# frc_operator_interface.net
KiCad netlist of a schematic drawn in EAGLE
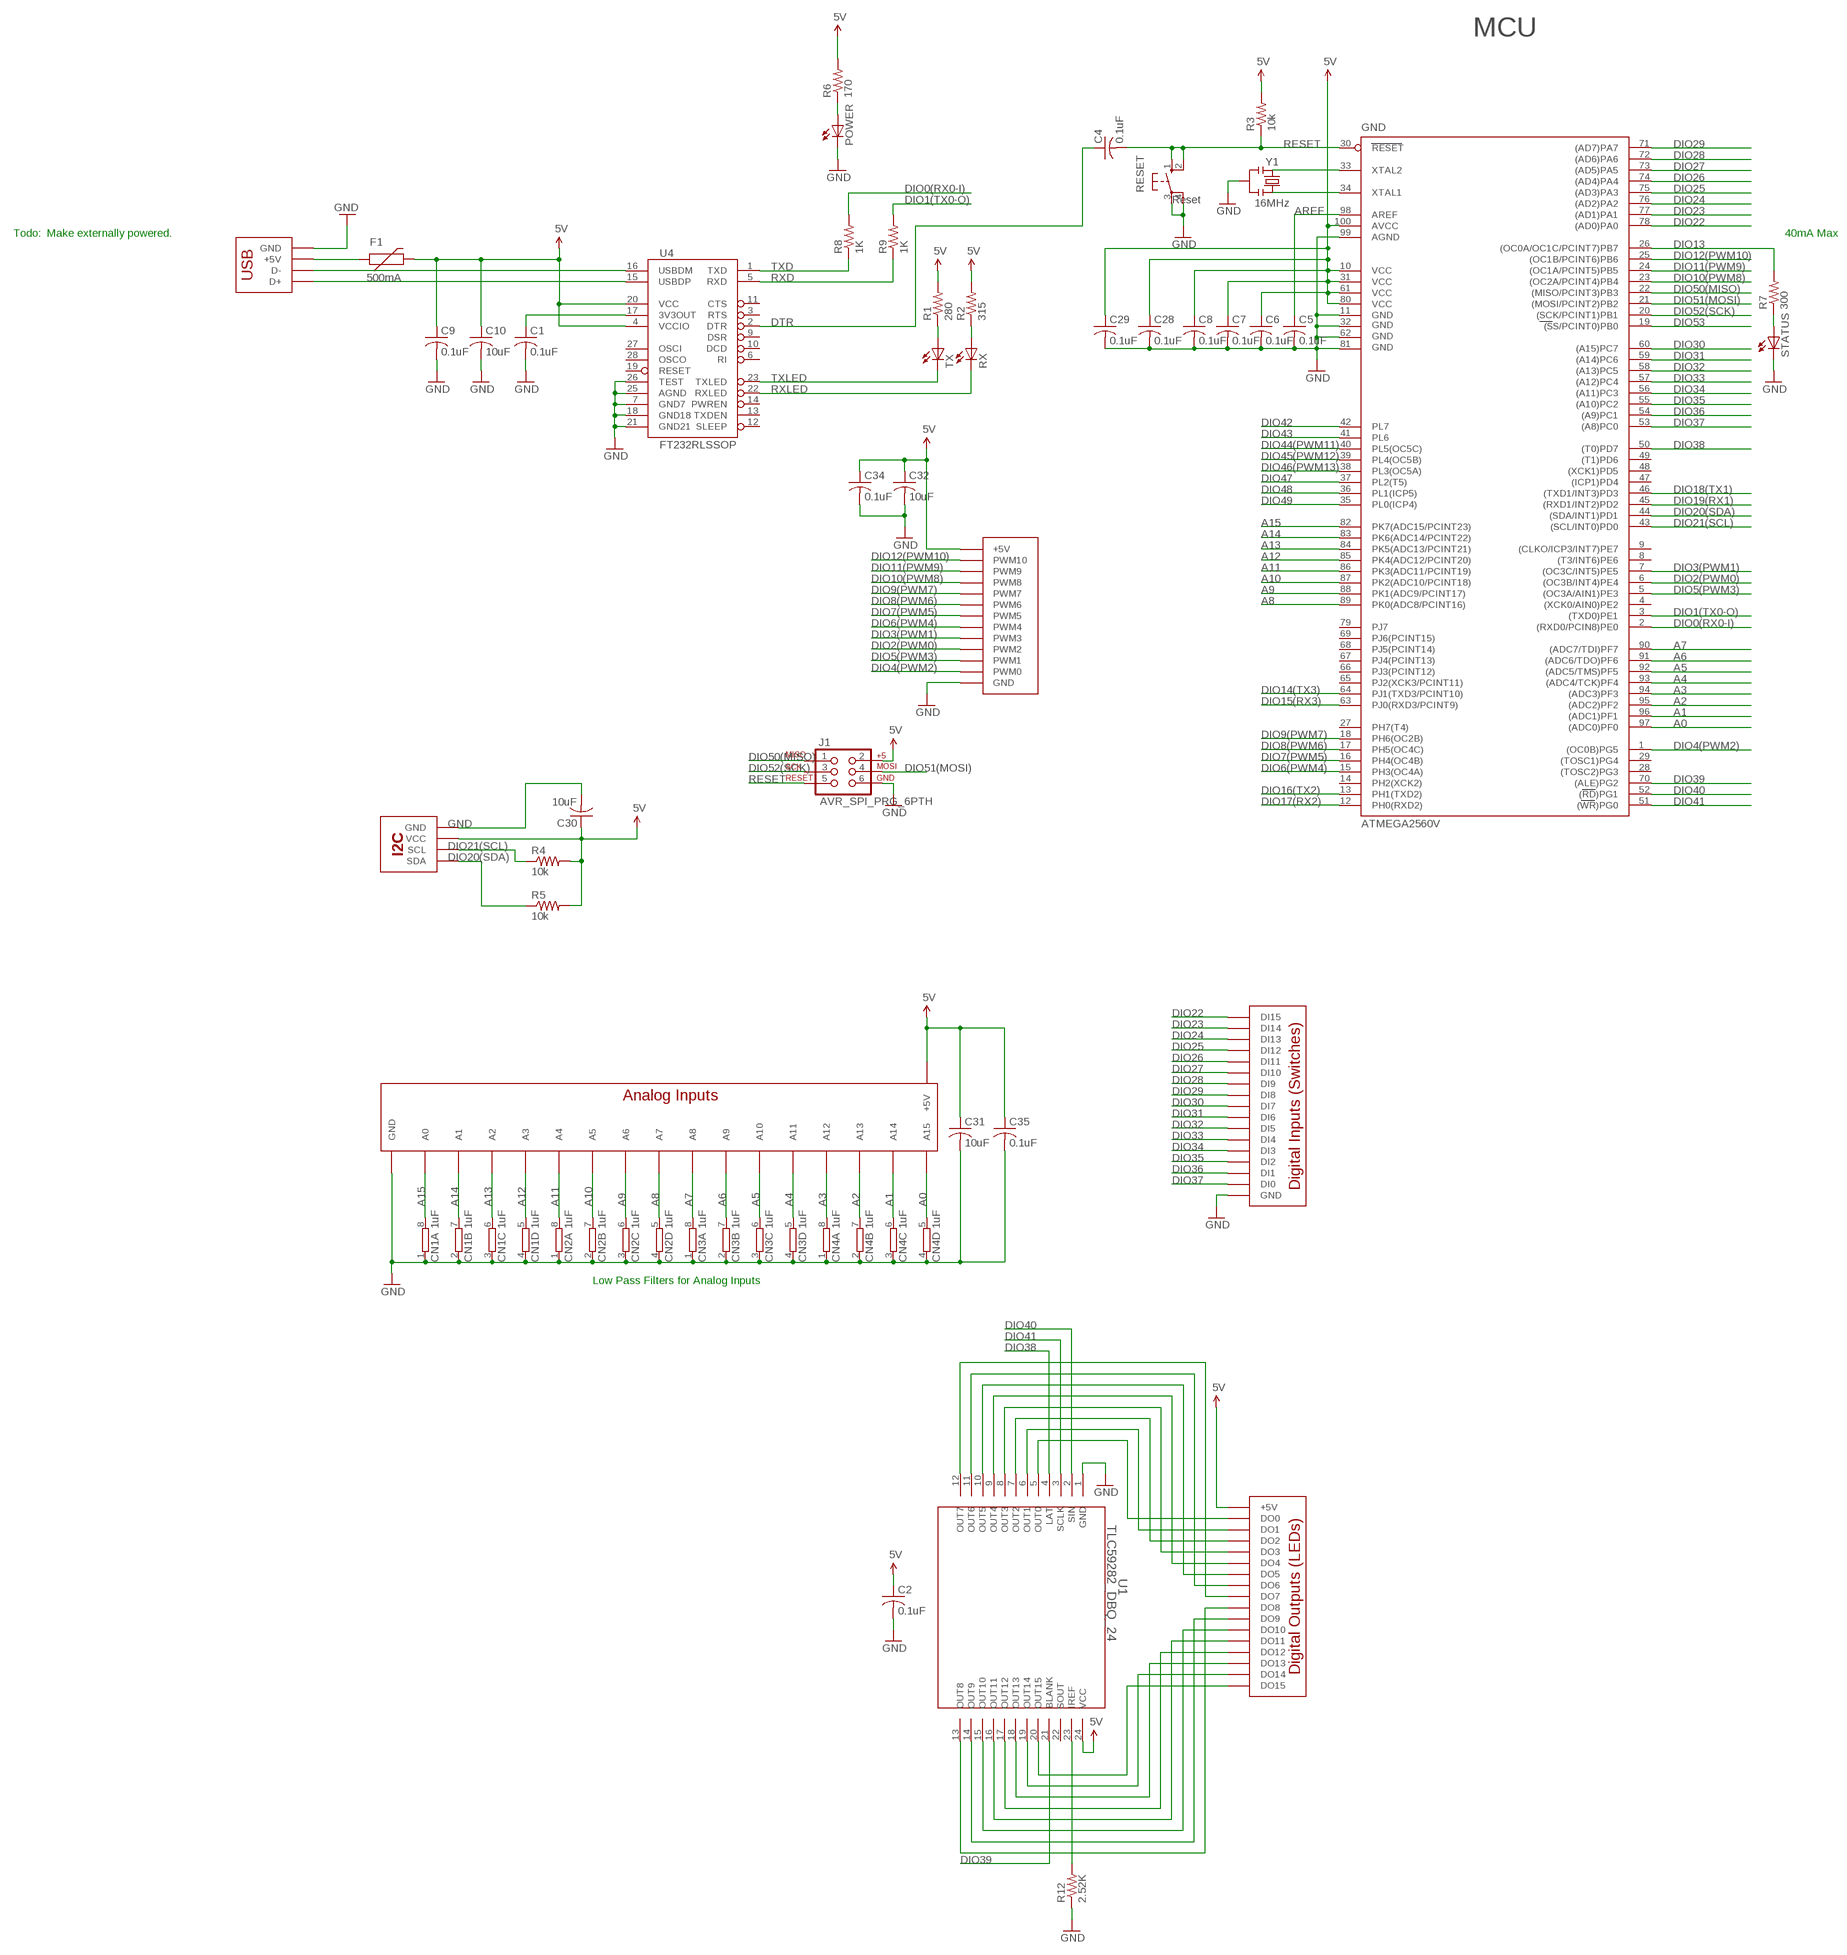
[diagram p0: schematic, sheet 1]

(export (version "E")
  (design (tool "Eeschema 10.0.6"))
  (components
    (comp (ref "C1")
      (value "0.1uF")
      (footprint "eagle-import:C1206")
      (libsource (lib "eagle-import") (part "C-USC1206"))
    )
    (comp (ref "C2")
      (value "0.1uF")
      (footprint "eagle-import:C1206")
      (libsource (lib "eagle-import") (part "C-USC1206"))
    )
    (comp (ref "C4")
      (value "0.1uF")
      (footprint "eagle-import:C1206")
      (libsource (lib "eagle-import") (part "C-USC1206"))
    )
    (comp (ref "C5")
      (value "0.1uF")
      (footprint "eagle-import:C1206")
      (libsource (lib "eagle-import") (part "C-USC1206"))
    )
    (comp (ref "C6")
      (value "0.1uF")
      (footprint "eagle-import:C1206")
      (libsource (lib "eagle-import") (part "C-USC1206"))
    )
    (comp (ref "C7")
      (value "0.1uF")
      (footprint "eagle-import:C1206")
      (libsource (lib "eagle-import") (part "C-USC1206"))
    )
    (comp (ref "C8")
      (value "0.1uF")
      (footprint "eagle-import:C1206")
      (libsource (lib "eagle-import") (part "C-USC1206"))
    )
    (comp (ref "C9")
      (value "0.1uF")
      (footprint "eagle-import:C1206")
      (libsource (lib "eagle-import") (part "C-USC1206"))
    )
    (comp (ref "C10")
      (value "10uF")
      (footprint "eagle-import:C1206")
      (libsource (lib "eagle-import") (part "C-USC1206"))
    )
    (comp (ref "C28")
      (value "0.1uF")
      (footprint "eagle-import:C1206")
      (libsource (lib "eagle-import") (part "C-USC1206"))
    )
    (comp (ref "C29")
      (value "0.1uF")
      (footprint "eagle-import:C1206")
      (libsource (lib "eagle-import") (part "C-USC1206"))
    )
    (comp (ref "C30")
      (value "10uF")
      (footprint "eagle-import:C1206")
      (libsource (lib "eagle-import") (part "C-USC1206"))
    )
    (comp (ref "C31")
      (value "10uF")
      (footprint "eagle-import:C1206")
      (libsource (lib "eagle-import") (part "C-USC1206"))
    )
    (comp (ref "C32")
      (value "10uF")
      (footprint "eagle-import:C1206")
      (libsource (lib "eagle-import") (part "C-USC1206"))
    )
    (comp (ref "C34")
      (value "0.1uF")
      (footprint "eagle-import:C1206")
      (libsource (lib "eagle-import") (part "C-USC1206"))
    )
    (comp (ref "C35")
      (value "0.1uF")
      (footprint "eagle-import:C1206")
      (libsource (lib "eagle-import") (part "C-USC1206"))
    )
    (comp (ref "CN1")
      (value "1uF")
      (footprint "eagle-import:EXB38V")
      (libsource (lib "eagle-import") (part "4R-NEXB38V"))
    )
    (comp (ref "CN2")
      (value "1uF")
      (footprint "eagle-import:EXB38V")
      (libsource (lib "eagle-import") (part "4R-NEXB38V"))
    )
    (comp (ref "CN3")
      (value "1uF")
      (footprint "eagle-import:EXB38V")
      (libsource (lib "eagle-import") (part "4R-NEXB38V"))
    )
    (comp (ref "CN4")
      (value "1uF")
      (footprint "eagle-import:EXB38V")
      (libsource (lib "eagle-import") (part "4R-NEXB38V"))
    )
    (comp (ref "F1")
      (value "500mA")
      (footprint "eagle-import:PTC-1206")
      (libsource (lib "eagle-import") (part "PTCSMD"))
    )
    (comp (ref "GND")
      (value "ATMEGA2560AU")
      (footprint "eagle-import:TQFP100")
      (libsource (lib "eagle-import") (part "ATMEGA2560AU"))
    )
    (comp (ref "J1")
      (value "AVR_SPI_PRG_6PTH")
      (footprint "eagle-import:2X3")
      (libsource (lib "eagle-import") (part "AVR_SPI_PRG_6PTH"))
    )
    (comp (ref "POWER")
      (value "LED3MM")
      (footprint "eagle-import:LED3MM")
      (libsource (lib "eagle-import") (part "LED3MM"))
    )
    (comp (ref "R1")
      (value "280")
      (footprint "eagle-import:M1206")
      (libsource (lib "eagle-import") (part "R-US_M1206"))
    )
    (comp (ref "R2")
      (value "315")
      (footprint "eagle-import:M1206")
      (libsource (lib "eagle-import") (part "R-US_M1206"))
    )
    (comp (ref "R3")
      (value "10k")
      (footprint "eagle-import:M1206")
      (libsource (lib "eagle-import") (part "R-US_M1206"))
    )
    (comp (ref "R4")
      (value "10k")
      (footprint "eagle-import:M1206")
      (libsource (lib "eagle-import") (part "R-US_M1206"))
    )
    (comp (ref "R5")
      (value "10k")
      (footprint "eagle-import:M1206")
      (libsource (lib "eagle-import") (part "R-US_M1206"))
    )
    (comp (ref "R6")
      (value "170")
      (footprint "eagle-import:M1206")
      (libsource (lib "eagle-import") (part "R-US_M1206"))
    )
    (comp (ref "R7")
      (value "300")
      (footprint "eagle-import:M1206")
      (libsource (lib "eagle-import") (part "R-US_M1206"))
    )
    (comp (ref "R8")
      (value "1K")
      (footprint "eagle-import:M1206")
      (libsource (lib "eagle-import") (part "R-US_M1206"))
    )
    (comp (ref "R9")
      (value "1K")
      (footprint "eagle-import:M1206")
      (libsource (lib "eagle-import") (part "R-US_M1206"))
    )
    (comp (ref "R12")
      (value "2.52K")
      (footprint "eagle-import:M1206")
      (libsource (lib "eagle-import") (part "R-US_M1206"))
    )
    (comp (ref "RESET")
      (value "10-XX")
      (footprint "eagle-import:B3F-10XX")
      (fields (field (name "MPN") "B3F-1000"))
      (libsource (lib "eagle-import") (part "10-XX"))
    )
    (comp (ref "RX")
      (value "LED3MM")
      (footprint "eagle-import:LED3MM")
      (libsource (lib "eagle-import") (part "LED3MM"))
    )
    (comp (ref "STATUS")
      (value "LED3MM")
      (footprint "eagle-import:LED3MM")
      (libsource (lib "eagle-import") (part "LED3MM"))
    )
    (comp (ref "TX")
      (value "LED3MM")
      (footprint "eagle-import:LED3MM")
      (libsource (lib "eagle-import") (part "LED3MM"))
    )
    (comp (ref "U$2")
      (value "DIGITALIN")
      (footprint "eagle-import:DIGITALIN")
      (libsource (lib "eagle-import") (part "DIGITALIN"))
    )
    (comp (ref "U$10")
      (value "PWMHEADER")
      (footprint "eagle-import:PWMHEADER")
      (libsource (lib "eagle-import") (part "PWMHEADER"))
    )
    (comp (ref "U$11")
      (value "DIGITALOUTPUTS")
      (footprint "eagle-import:DIGITALOUT")
      (libsource (lib "eagle-import") (part "DIGITALOUTPUTS"))
    )
    (comp (ref "U$12")
      (value "ANALOGHEADER")
      (footprint "eagle-import:ANALOGHEADER")
      (libsource (lib "eagle-import") (part "ANALOGHEADER"))
    )
    (comp (ref "U$14")
      (value "UE27BC54130-USB")
      (footprint "eagle-import:UE27BC54130-USB")
      (libsource (lib "eagle-import") (part "UE27BC54130-USB"))
    )
    (comp (ref "U$15")
      (value "I2CHEADER")
      (footprint "eagle-import:I2CHEADER")
      (libsource (lib "eagle-import") (part "I2CHEADER"))
    )
    (comp (ref "U1")
      (value "TLC59282_DBQ_24")
      (footprint "eagle-import:DBQ24")
      (fields
        (field (name "GENERIC_PART_NUMBER") "TLC59282")
        (field (name "MANUFACTURER") "Texas Instruments")
        (field (name "MANUFACTURER_PART_NUMBER") "tlc59282_dbq_24")
      )
      (libsource (lib "eagle-import") (part "TLC59282_DBQ_24"))
    )
    (comp (ref "U4")
      (value "FT232RLSSOP")
      (footprint "eagle-import:SSOP28DB")
      (libsource (lib "eagle-import") (part "FT232RLSSOP"))
    )
    (comp (ref "Y1")
      (value "RESONATORSMD")
      (footprint "eagle-import:RESONATOR-SMD")
      (libsource (lib "eagle-import") (part "RESONATORSMD"))
    )
  )
  (nets
    (net (code "1") (name "/A0") (class "Default")
      (node (ref "CN4") (pin "5") (pinfunction "2_5") (pintype "passive"))
      (node (ref "GND") (pin "97") (pinfunction "(ADC0)PF0_97") (pintype "bidirectional"))
      (node (ref "U$12") (pin "15") (pinfunction "A15_15") (pintype "bidirectional"))
    )
    (net (code "2") (name "/A1") (class "Default")
      (node (ref "CN4") (pin "6") (pinfunction "2_6") (pintype "passive"))
      (node (ref "GND") (pin "96") (pinfunction "(ADC1)PF1_96") (pintype "bidirectional"))
      (node (ref "U$12") (pin "14") (pinfunction "A14_14") (pintype "bidirectional"))
    )
    (net (code "3") (name "/A2") (class "Default")
      (node (ref "CN4") (pin "7") (pinfunction "2_7") (pintype "passive"))
      (node (ref "GND") (pin "95") (pinfunction "(ADC2)PF2_95") (pintype "bidirectional"))
      (node (ref "U$12") (pin "13") (pinfunction "A13_13") (pintype "bidirectional"))
    )
    (net (code "4") (name "/A3") (class "Default")
      (node (ref "CN4") (pin "8") (pinfunction "2_8") (pintype "passive"))
      (node (ref "GND") (pin "94") (pinfunction "(ADC3)PF3_94") (pintype "bidirectional"))
      (node (ref "U$12") (pin "12") (pinfunction "A12_12") (pintype "bidirectional"))
    )
    (net (code "5") (name "/A4") (class "Default")
      (node (ref "CN3") (pin "5") (pinfunction "2_5") (pintype "passive"))
      (node (ref "GND") (pin "93") (pinfunction "(ADC4/TCK)PF4_93") (pintype "bidirectional"))
      (node (ref "U$12") (pin "11") (pinfunction "A11_11") (pintype "bidirectional"))
    )
    (net (code "6") (name "/A5") (class "Default")
      (node (ref "CN3") (pin "6") (pinfunction "2_6") (pintype "passive"))
      (node (ref "GND") (pin "92") (pinfunction "(ADC5/TMS)PF5_92") (pintype "bidirectional"))
      (node (ref "U$12") (pin "10") (pinfunction "A10_10") (pintype "bidirectional"))
    )
    (net (code "7") (name "/A6") (class "Default")
      (node (ref "CN3") (pin "7") (pinfunction "2_7") (pintype "passive"))
      (node (ref "GND") (pin "91") (pinfunction "(ADC6/TDO)PF6_91") (pintype "bidirectional"))
      (node (ref "U$12") (pin "9") (pinfunction "A9_9") (pintype "bidirectional"))
    )
    (net (code "8") (name "/A7") (class "Default")
      (node (ref "CN3") (pin "8") (pinfunction "2_8") (pintype "passive"))
      (node (ref "GND") (pin "90") (pinfunction "(ADC7/TDI)PF7_90") (pintype "bidirectional"))
      (node (ref "U$12") (pin "8") (pinfunction "A8_8") (pintype "bidirectional"))
    )
    (net (code "9") (name "/A8") (class "Default")
      (node (ref "CN2") (pin "5") (pinfunction "2_5") (pintype "passive"))
      (node (ref "GND") (pin "89") (pinfunction "PK0(ADC8/PCINT16)_89") (pintype "bidirectional"))
      (node (ref "U$12") (pin "7") (pinfunction "A7_7") (pintype "bidirectional"))
    )
    (net (code "10") (name "/A9") (class "Default")
      (node (ref "CN2") (pin "6") (pinfunction "2_6") (pintype "passive"))
      (node (ref "GND") (pin "88") (pinfunction "PK1(ADC9/PCINT17)_88") (pintype "bidirectional"))
      (node (ref "U$12") (pin "6") (pinfunction "A6_6") (pintype "bidirectional"))
    )
    (net (code "11") (name "/A10") (class "Default")
      (node (ref "CN2") (pin "7") (pinfunction "2_7") (pintype "passive"))
      (node (ref "GND") (pin "87") (pinfunction "PK2(ADC10/PCINT18)_87") (pintype "bidirectional"))
      (node (ref "U$12") (pin "5") (pinfunction "A5_5") (pintype "bidirectional"))
    )
    (net (code "12") (name "/A11") (class "Default")
      (node (ref "CN2") (pin "8") (pinfunction "2_8") (pintype "passive"))
      (node (ref "GND") (pin "86") (pinfunction "PK3(ADC11/PCINT19)_86") (pintype "bidirectional"))
      (node (ref "U$12") (pin "4") (pinfunction "A4_4") (pintype "bidirectional"))
    )
    (net (code "13") (name "/A12") (class "Default")
      (node (ref "CN1") (pin "5") (pinfunction "2_5") (pintype "passive"))
      (node (ref "GND") (pin "85") (pinfunction "PK4(ADC12/PCINT20)_85") (pintype "bidirectional"))
      (node (ref "U$12") (pin "3") (pinfunction "A3_3") (pintype "bidirectional"))
    )
    (net (code "14") (name "/A13") (class "Default")
      (node (ref "CN1") (pin "6") (pinfunction "2_6") (pintype "passive"))
      (node (ref "GND") (pin "84") (pinfunction "PK5(ADC13/PCINT21)_84") (pintype "bidirectional"))
      (node (ref "U$12") (pin "2") (pinfunction "A2_2") (pintype "bidirectional"))
    )
    (net (code "15") (name "/A14") (class "Default")
      (node (ref "CN1") (pin "7") (pinfunction "2_7") (pintype "passive"))
      (node (ref "GND") (pin "83") (pinfunction "PK6(ADC14/PCINT22)_83") (pintype "bidirectional"))
      (node (ref "U$12") (pin "1") (pinfunction "A1_1") (pintype "bidirectional"))
    )
    (net (code "16") (name "/A15") (class "Default")
      (node (ref "CN1") (pin "8") (pinfunction "2_8") (pintype "passive"))
      (node (ref "GND") (pin "82") (pinfunction "PK7(ADC15/PCINT23)_82") (pintype "bidirectional"))
      (node (ref "U$12") (pin "0") (pinfunction "A0_0") (pintype "bidirectional"))
    )
    (net (code "17") (name "/AREF") (class "Default")
      (node (ref "C5") (pin "1") (pinfunction "1_1") (pintype "passive"))
      (node (ref "GND") (pin "98") (pinfunction "AREF_98") (pintype "bidirectional"))
    )
    (net (code "18") (name "/DIO0(RX0-I)") (class "Default")
      (node (ref "GND") (pin "2") (pinfunction "(RXD0/PCIN8)PE0_2") (pintype "bidirectional"))
      (node (ref "R8") (pin "2") (pinfunction "2_2") (pintype "passive"))
    )
    (net (code "19") (name "/DIO1(TX0-O)") (class "Default")
      (node (ref "GND") (pin "3") (pinfunction "(TXD0)PE1_3") (pintype "bidirectional"))
      (node (ref "R9") (pin "2") (pinfunction "2_2") (pintype "passive"))
    )
    (net (code "20") (name "/DIO2(PWM0)") (class "Default")
      (node (ref "GND") (pin "6") (pinfunction "(OC3B/INT4)PE4_6") (pintype "bidirectional"))
      (node (ref "U$10") (pin "2") (pinfunction "PWM2_2") (pintype "output"))
    )
    (net (code "21") (name "/DIO3(PWM1)") (class "Default")
      (node (ref "GND") (pin "7") (pinfunction "(OC3C/INT5)PE5_7") (pintype "bidirectional"))
      (node (ref "U$10") (pin "3") (pinfunction "PWM3_3") (pintype "output"))
    )
    (net (code "22") (name "/DIO4(PWM2)") (class "Default")
      (node (ref "GND") (pin "1") (pinfunction "(OC0B)PG5_1") (pintype "bidirectional"))
      (node (ref "U$10") (pin "0") (pinfunction "PWM0_0") (pintype "output"))
    )
    (net (code "23") (name "/DIO5(PWM3)") (class "Default")
      (node (ref "GND") (pin "5") (pinfunction "(OC3A/AIN1)PE3_5") (pintype "bidirectional"))
      (node (ref "U$10") (pin "1") (pinfunction "PWM1_1") (pintype "output"))
    )
    (net (code "24") (name "/DIO6(PWM4)") (class "Default")
      (node (ref "GND") (pin "15") (pinfunction "PH3(OC4A)_15") (pintype "bidirectional"))
      (node (ref "U$10") (pin "4") (pinfunction "PWM4_4") (pintype "output"))
    )
    (net (code "25") (name "/DIO7(PWM5)") (class "Default")
      (node (ref "GND") (pin "16") (pinfunction "PH4(OC4B)_16") (pintype "bidirectional"))
      (node (ref "U$10") (pin "5") (pinfunction "PWM5_5") (pintype "output"))
    )
    (net (code "26") (name "/DIO8(PWM6)") (class "Default")
      (node (ref "GND") (pin "17") (pinfunction "PH5(OC4C)_17") (pintype "bidirectional"))
      (node (ref "U$10") (pin "6") (pinfunction "PWM6_6") (pintype "output"))
    )
    (net (code "27") (name "/DIO9(PWM7)") (class "Default")
      (node (ref "GND") (pin "18") (pinfunction "PH6(OC2B)_18") (pintype "bidirectional"))
      (node (ref "U$10") (pin "7") (pinfunction "PWM7_7") (pintype "output"))
    )
    (net (code "28") (name "/DIO10(PWM8)") (class "Default")
      (node (ref "GND") (pin "23") (pinfunction "(OC2A/PCINT4)PB4_23") (pintype "bidirectional"))
      (node (ref "U$10") (pin "8") (pinfunction "PWM8_8") (pintype "output"))
    )
    (net (code "29") (name "/DIO11(PWM9)") (class "Default")
      (node (ref "GND") (pin "24") (pinfunction "(OC1A/PCINT5)PB5_24") (pintype "bidirectional"))
      (node (ref "U$10") (pin "9") (pinfunction "PWM9_9") (pintype "output"))
    )
    (net (code "30") (name "/DIO12(PWM10)") (class "Default")
      (node (ref "GND") (pin "25") (pinfunction "(OC1B/PCINT6)PB6_25") (pintype "bidirectional"))
      (node (ref "U$10") (pin "10") (pinfunction "PWM10_10") (pintype "output"))
    )
    (net (code "31") (name "/DIO13") (class "Default")
      (node (ref "GND") (pin "26") (pinfunction "(OC0A/OC1C/PCINT7)PB7_26") (pintype "bidirectional"))
      (node (ref "R7") (pin "2") (pinfunction "2_2") (pintype "passive"))
    )
    (net (code "32") (name "/DIO14(TX3)") (class "Default")
      (node (ref "GND") (pin "64") (pinfunction "PJ1(TXD3/PCINT10)_64") (pintype "bidirectional"))
    )
    (net (code "33") (name "/DIO15(RX3)") (class "Default")
      (node (ref "GND") (pin "63") (pinfunction "PJ0(RXD3/PCINT9)_63") (pintype "bidirectional"))
    )
    (net (code "34") (name "/DIO16(TX2)") (class "Default")
      (node (ref "GND") (pin "13") (pinfunction "PH1(TXD2)_13") (pintype "bidirectional"))
    )
    (net (code "35") (name "/DIO17(RX2)") (class "Default")
      (node (ref "GND") (pin "12") (pinfunction "PH0(RXD2)_12") (pintype "bidirectional"))
    )
    (net (code "36") (name "/DIO18(TX1)") (class "Default")
      (node (ref "GND") (pin "46") (pinfunction "(TXD1/INT3)PD3_46") (pintype "bidirectional"))
    )
    (net (code "37") (name "/DIO19(RX1)") (class "Default")
      (node (ref "GND") (pin "45") (pinfunction "(RXD1/INT2)PD2_45") (pintype "bidirectional"))
    )
    (net (code "38") (name "/DIO20(SDA)") (class "Default")
      (node (ref "GND") (pin "44") (pinfunction "(SDA/INT1)PD1_44") (pintype "bidirectional"))
      (node (ref "R5") (pin "1") (pinfunction "1_1") (pintype "passive"))
      (node (ref "U$15") (pin "SDA@0") (pinfunction "SDA_SDA@0") (pintype "bidirectional"))
      (node (ref "U$15") (pin "SDA@1") (pinfunction "SDA_SDA@1") (pintype "bidirectional"))
      (node (ref "U$15") (pin "SDA@2") (pinfunction "SDA_SDA@2") (pintype "bidirectional"))
      (node (ref "U$15") (pin "SDA@3") (pinfunction "SDA_SDA@3") (pintype "bidirectional"))
    )
    (net (code "39") (name "/DIO21(SCL)") (class "Default")
      (node (ref "GND") (pin "43") (pinfunction "(SCL/INT0)PD0_43") (pintype "bidirectional"))
      (node (ref "R4") (pin "1") (pinfunction "1_1") (pintype "passive"))
      (node (ref "U$15") (pin "SCL@0") (pinfunction "SCL_SCL@0") (pintype "bidirectional"))
      (node (ref "U$15") (pin "SCL@1") (pinfunction "SCL_SCL@1") (pintype "bidirectional"))
      (node (ref "U$15") (pin "SCL@2") (pinfunction "SCL_SCL@2") (pintype "bidirectional"))
      (node (ref "U$15") (pin "SCL@3") (pinfunction "SCL_SCL@3") (pintype "bidirectional"))
    )
    (net (code "40") (name "/DIO22") (class "Default")
      (node (ref "GND") (pin "78") (pinfunction "(AD0)PA0_78") (pintype "bidirectional"))
      (node (ref "U$2") (pin "DI15") (pinfunction "DI15_DI15") (pintype "bidirectional"))
    )
    (net (code "41") (name "/DIO23") (class "Default")
      (node (ref "GND") (pin "77") (pinfunction "(AD1)PA1_77") (pintype "bidirectional"))
      (node (ref "U$2") (pin "DI14") (pinfunction "DI14_DI14") (pintype "bidirectional"))
    )
    (net (code "42") (name "/DIO24") (class "Default")
      (node (ref "GND") (pin "76") (pinfunction "(AD2)PA2_76") (pintype "bidirectional"))
      (node (ref "U$2") (pin "DI13") (pinfunction "DI13_DI13") (pintype "bidirectional"))
    )
    (net (code "43") (name "/DIO25") (class "Default")
      (node (ref "GND") (pin "75") (pinfunction "(AD3)PA3_75") (pintype "bidirectional"))
      (node (ref "U$2") (pin "DI12") (pinfunction "DI12_DI12") (pintype "bidirectional"))
    )
    (net (code "44") (name "/DIO26") (class "Default")
      (node (ref "GND") (pin "74") (pinfunction "(AD4)PA4_74") (pintype "bidirectional"))
      (node (ref "U$2") (pin "DI11") (pinfunction "DI11_DI11") (pintype "bidirectional"))
    )
    (net (code "45") (name "/DIO27") (class "Default")
      (node (ref "GND") (pin "73") (pinfunction "(AD5)PA5_73") (pintype "bidirectional"))
      (node (ref "U$2") (pin "DI10") (pinfunction "DI10_DI10") (pintype "bidirectional"))
    )
    (net (code "46") (name "/DIO28") (class "Default")
      (node (ref "GND") (pin "72") (pinfunction "(AD6)PA6_72") (pintype "bidirectional"))
      (node (ref "U$2") (pin "DI9") (pinfunction "DI9_DI9") (pintype "bidirectional"))
    )
    (net (code "47") (name "/DIO29") (class "Default")
      (node (ref "GND") (pin "71") (pinfunction "(AD7)PA7_71") (pintype "bidirectional"))
      (node (ref "U$2") (pin "DI8") (pinfunction "DI8_DI8") (pintype "bidirectional"))
    )
    (net (code "48") (name "/DIO30") (class "Default")
      (node (ref "GND") (pin "60") (pinfunction "(A15)PC7_60") (pintype "bidirectional"))
      (node (ref "U$2") (pin "DI7") (pinfunction "DI7_DI7") (pintype "bidirectional"))
    )
    (net (code "49") (name "/DIO31") (class "Default")
      (node (ref "GND") (pin "59") (pinfunction "(A14)PC6_59") (pintype "bidirectional"))
      (node (ref "U$2") (pin "DI6") (pinfunction "DI6_DI6") (pintype "bidirectional"))
    )
    (net (code "50") (name "/DIO32") (class "Default")
      (node (ref "GND") (pin "58") (pinfunction "(A13)PC5_58") (pintype "bidirectional"))
      (node (ref "U$2") (pin "DI5") (pinfunction "DI5_DI5") (pintype "bidirectional"))
    )
    (net (code "51") (name "/DIO33") (class "Default")
      (node (ref "GND") (pin "57") (pinfunction "(A12)PC4_57") (pintype "bidirectional"))
      (node (ref "U$2") (pin "DI4") (pinfunction "DI4_DI4") (pintype "bidirectional"))
    )
    (net (code "52") (name "/DIO34") (class "Default")
      (node (ref "GND") (pin "56") (pinfunction "(A11)PC3_56") (pintype "bidirectional"))
      (node (ref "U$2") (pin "DI3") (pinfunction "DI3_DI3") (pintype "bidirectional"))
    )
    (net (code "53") (name "/DIO35") (class "Default")
      (node (ref "GND") (pin "55") (pinfunction "(A10)PC2_55") (pintype "bidirectional"))
      (node (ref "U$2") (pin "DI2") (pinfunction "DI2_DI2") (pintype "bidirectional"))
    )
    (net (code "54") (name "/DIO36") (class "Default")
      (node (ref "GND") (pin "54") (pinfunction "(A9)PC1_54") (pintype "bidirectional"))
      (node (ref "U$2") (pin "DI1") (pinfunction "DI1_DI1") (pintype "bidirectional"))
    )
    (net (code "55") (name "/DIO37") (class "Default")
      (node (ref "GND") (pin "53") (pinfunction "(A8)PC0_53") (pintype "bidirectional"))
      (node (ref "U$2") (pin "DI0") (pinfunction "DI0_DI0") (pintype "bidirectional"))
    )
    (net (code "56") (name "/DIO38") (class "Default")
      (node (ref "GND") (pin "50") (pinfunction "(T0)PD7_50") (pintype "bidirectional"))
      (node (ref "U1") (pin "4") (pinfunction "LAT_4") (pintype "input"))
    )
    (net (code "57") (name "/DIO39") (class "Default")
      (node (ref "GND") (pin "70") (pinfunction "(ALE)PG2_70") (pintype "bidirectional"))
      (node (ref "U1") (pin "21") (pinfunction "BLANK_21") (pintype "input"))
    )
    (net (code "58") (name "/DIO40") (class "Default")
      (node (ref "GND") (pin "52") (pinfunction "(RD)PG1_52") (pintype "bidirectional"))
      (node (ref "U1") (pin "2") (pinfunction "SIN_2") (pintype "input"))
    )
    (net (code "59") (name "/DIO41") (class "Default")
      (node (ref "GND") (pin "51") (pinfunction "(WR)PG0_51") (pintype "bidirectional"))
      (node (ref "U1") (pin "3") (pinfunction "SCLK_3") (pintype "input"))
    )
    (net (code "60") (name "/DIO42") (class "Default")
      (node (ref "GND") (pin "42") (pinfunction "PL7_42") (pintype "bidirectional"))
    )
    (net (code "61") (name "/DIO43") (class "Default")
      (node (ref "GND") (pin "41") (pinfunction "PL6_41") (pintype "bidirectional"))
    )
    (net (code "62") (name "/DIO44(PWM11)") (class "Default")
      (node (ref "GND") (pin "40") (pinfunction "PL5(OC5C)_40") (pintype "bidirectional"))
    )
    (net (code "63") (name "/DIO45(PWM12)") (class "Default")
      (node (ref "GND") (pin "39") (pinfunction "PL4(OC5B)_39") (pintype "bidirectional"))
    )
    (net (code "64") (name "/DIO46(PWM13)") (class "Default")
      (node (ref "GND") (pin "38") (pinfunction "PL3(OC5A)_38") (pintype "bidirectional"))
    )
    (net (code "65") (name "/DIO47") (class "Default")
      (node (ref "GND") (pin "37") (pinfunction "PL2(T5)_37") (pintype "bidirectional"))
    )
    (net (code "66") (name "/DIO48") (class "Default")
      (node (ref "GND") (pin "36") (pinfunction "PL1(ICP5)_36") (pintype "bidirectional"))
    )
    (net (code "67") (name "/DIO49") (class "Default")
      (node (ref "GND") (pin "35") (pinfunction "PL0(ICP4)_35") (pintype "bidirectional"))
    )
    (net (code "68") (name "/DIO50(MISO)") (class "Default")
      (node (ref "GND") (pin "22") (pinfunction "(MISO/PCINT3)PB3_22") (pintype "bidirectional"))
      (node (ref "J1") (pin "1") (pinfunction "1_1") (pintype "passive"))
    )
    (net (code "69") (name "/DIO51(MOSI)") (class "Default")
      (node (ref "GND") (pin "21") (pinfunction "(MOSI/PCINT2)PB2_21") (pintype "bidirectional"))
      (node (ref "J1") (pin "4") (pinfunction "4_4") (pintype "passive"))
    )
    (net (code "70") (name "/DIO52(SCK)") (class "Default")
      (node (ref "GND") (pin "20") (pinfunction "(SCK/PCINT1)PB1_20") (pintype "bidirectional"))
      (node (ref "J1") (pin "3") (pinfunction "3_3") (pintype "passive"))
    )
    (net (code "71") (name "/DIO53") (class "Default")
      (node (ref "GND") (pin "19") (pinfunction "(SS/PCINT0)PB0_19") (pintype "bidirectional"))
    )
    (net (code "72") (name "/DTR") (class "Default")
      (node (ref "C4") (pin "1") (pinfunction "1_1") (pintype "passive"))
      (node (ref "U4") (pin "2") (pinfunction "DTR_2") (pintype "output"))
    )
    (net (code "73") (name "/RESET") (class "Default")
      (node (ref "C4") (pin "2") (pinfunction "2_2") (pintype "passive"))
      (node (ref "GND") (pin "30") (pinfunction "RESET_30") (pintype "input"))
      (node (ref "J1") (pin "5") (pinfunction "5_5") (pintype "passive"))
      (node (ref "R3") (pin "1") (pinfunction "1_1") (pintype "passive"))
      (node (ref "RESET") (pin "1") (pinfunction "S_1") (pintype "passive"))
      (node (ref "RESET") (pin "2") (pinfunction "S1_2") (pintype "passive"))
    )
    (net (code "74") (name "/RXD") (class "Default")
      (node (ref "R9") (pin "1") (pinfunction "1_1") (pintype "passive"))
      (node (ref "U4") (pin "5") (pinfunction "RXD_5") (pintype "input"))
    )
    (net (code "75") (name "/RXLED") (class "Default")
      (node (ref "RX") (pin "K") (pinfunction "C_K") (pintype "passive"))
      (node (ref "U4") (pin "22") (pinfunction "RXLED_22") (pintype "input"))
    )
    (net (code "76") (name "/TXD") (class "Default")
      (node (ref "R8") (pin "1") (pinfunction "1_1") (pintype "passive"))
      (node (ref "U4") (pin "1") (pinfunction "TXD_1") (pintype "output"))
    )
    (net (code "77") (name "/TXLED") (class "Default")
      (node (ref "TX") (pin "K") (pinfunction "C_K") (pintype "passive"))
      (node (ref "U4") (pin "23") (pinfunction "TXLED_23") (pintype "input"))
    )
    (net (code "78") (name "5V") (class "Default")
      (node (ref "C10") (pin "1") (pinfunction "1_1") (pintype "passive"))
      (node (ref "C2") (pin "1") (pinfunction "1_1") (pintype "passive"))
      (node (ref "C28") (pin "1") (pinfunction "1_1") (pintype "passive"))
      (node (ref "C29") (pin "1") (pinfunction "1_1") (pintype "passive"))
      (node (ref "C30") (pin "1") (pinfunction "1_1") (pintype "passive"))
      (node (ref "C31") (pin "1") (pinfunction "1_1") (pintype "passive"))
      (node (ref "C32") (pin "1") (pinfunction "1_1") (pintype "passive"))
      (node (ref "C34") (pin "1") (pinfunction "1_1") (pintype "passive"))
      (node (ref "C35") (pin "1") (pinfunction "1_1") (pintype "passive"))
      (node (ref "C6") (pin "1") (pinfunction "1_1") (pintype "passive"))
      (node (ref "C7") (pin "1") (pinfunction "1_1") (pintype "passive"))
      (node (ref "C8") (pin "1") (pinfunction "1_1") (pintype "passive"))
      (node (ref "C9") (pin "1") (pinfunction "1_1") (pintype "passive"))
      (node (ref "F1") (pin "2") (pinfunction "2_2") (pintype "bidirectional"))
      (node (ref "GND") (pin "10") (pinfunction "VCC_10") (pintype "power_in"))
      (node (ref "GND") (pin "100") (pinfunction "AVCC_100") (pintype "power_in"))
      (node (ref "GND") (pin "31") (pinfunction "VCC1_31") (pintype "power_in"))
      (node (ref "GND") (pin "61") (pinfunction "VCC2_61") (pintype "power_in"))
      (node (ref "GND") (pin "80") (pinfunction "VCC3_80") (pintype "power_in"))
      (node (ref "J1") (pin "2") (pinfunction "2_2") (pintype "passive"))
      (node (ref "R1") (pin "2") (pinfunction "2_2") (pintype "passive"))
      (node (ref "R2") (pin "2") (pinfunction "2_2") (pintype "passive"))
      (node (ref "R3") (pin "2") (pinfunction "2_2") (pintype "passive"))
      (node (ref "R4") (pin "2") (pinfunction "2_2") (pintype "passive"))
      (node (ref "R5") (pin "2") (pinfunction "2_2") (pintype "passive"))
      (node (ref "R6") (pin "2") (pinfunction "2_2") (pintype "passive"))
      (node (ref "U$10") (pin "+5V@10") (pinfunction "+5V_+5V@10") (pintype "power_in"))
      (node (ref "U$10") (pin "+5V@11") (pinfunction "+5V_+5V@11") (pintype "power_in"))
      (node (ref "U$10") (pin "+5V@12") (pinfunction "+5V_+5V@12") (pintype "power_in"))
      (node (ref "U$10") (pin "+5V@13") (pinfunction "+5V_+5V@13") (pintype "power_in"))
      (node (ref "U$10") (pin "+5V@3") (pinfunction "+5V_+5V@3") (pintype "power_in"))
      (node (ref "U$10") (pin "+5V@4") (pinfunction "+5V_+5V@4") (pintype "power_in"))
      (node (ref "U$10") (pin "+5V@5") (pinfunction "+5V_+5V@5") (pintype "power_in"))
      (node (ref "U$10") (pin "+5V@6") (pinfunction "+5V_+5V@6") (pintype "power_in"))
      (node (ref "U$10") (pin "+5V@7") (pinfunction "+5V_+5V@7") (pintype "power_in"))
      (node (ref "U$10") (pin "+5V@8") (pinfunction "+5V_+5V@8") (pintype "power_in"))
      (node (ref "U$10") (pin "+5V@9") (pinfunction "+5V_+5V@9") (pintype "power_in"))
      (node (ref "U$11") (pin "+5V@0") (pinfunction "+5V_+5V@0") (pintype "power_in"))
      (node (ref "U$11") (pin "+5V@1") (pinfunction "+5V_+5V@1") (pintype "power_in"))
      (node (ref "U$11") (pin "+5V@10") (pinfunction "+5V_+5V@10") (pintype "power_in"))
      (node (ref "U$11") (pin "+5V@11") (pinfunction "+5V_+5V@11") (pintype "power_in"))
      (node (ref "U$11") (pin "+5V@12") (pinfunction "+5V_+5V@12") (pintype "power_in"))
      (node (ref "U$11") (pin "+5V@13") (pinfunction "+5V_+5V@13") (pintype "power_in"))
      (node (ref "U$11") (pin "+5V@14") (pinfunction "+5V_+5V@14") (pintype "power_in"))
      (node (ref "U$11") (pin "+5V@15") (pinfunction "+5V_+5V@15") (pintype "power_in"))
      (node (ref "U$11") (pin "+5V@2") (pinfunction "+5V_+5V@2") (pintype "power_in"))
      (node (ref "U$11") (pin "+5V@3") (pinfunction "+5V_+5V@3") (pintype "power_in"))
      (node (ref "U$11") (pin "+5V@4") (pinfunction "+5V_+5V@4") (pintype "power_in"))
      (node (ref "U$11") (pin "+5V@5") (pinfunction "+5V_+5V@5") (pintype "power_in"))
      (node (ref "U$11") (pin "+5V@6") (pinfunction "+5V_+5V@6") (pintype "power_in"))
      (node (ref "U$11") (pin "+5V@7") (pinfunction "+5V_+5V@7") (pintype "power_in"))
      (node (ref "U$11") (pin "+5V@8") (pinfunction "+5V_+5V@8") (pintype "power_in"))
      (node (ref "U$11") (pin "+5V@9") (pinfunction "+5V_+5V@9") (pintype "power_in"))
      (node (ref "U$12") (pin "+5V@0") (pinfunction "+5V_+5V@0") (pintype "bidirectional"))
      (node (ref "U$12") (pin "+5V@1") (pinfunction "+5V_+5V@1") (pintype "bidirectional"))
      (node (ref "U$12") (pin "+5V@10") (pinfunction "+5V_+5V@10") (pintype "bidirectional"))
      (node (ref "U$12") (pin "+5V@11") (pinfunction "+5V_+5V@11") (pintype "bidirectional"))
      (node (ref "U$12") (pin "+5V@12") (pinfunction "+5V_+5V@12") (pintype "bidirectional"))
      (node (ref "U$12") (pin "+5V@13") (pinfunction "+5V_+5V@13") (pintype "bidirectional"))
      (node (ref "U$12") (pin "+5V@14") (pinfunction "+5V_+5V@14") (pintype "bidirectional"))
      (node (ref "U$12") (pin "+5V@15") (pinfunction "+5V_+5V@15") (pintype "bidirectional"))
      (node (ref "U$12") (pin "+5V@2") (pinfunction "+5V_+5V@2") (pintype "bidirectional"))
      (node (ref "U$12") (pin "+5V@3") (pinfunction "+5V_+5V@3") (pintype "bidirectional"))
      (node (ref "U$12") (pin "+5V@4") (pinfunction "+5V_+5V@4") (pintype "bidirectional"))
      (node (ref "U$12") (pin "+5V@5") (pinfunction "+5V_+5V@5") (pintype "bidirectional"))
      (node (ref "U$12") (pin "+5V@6") (pinfunction "+5V_+5V@6") (pintype "bidirectional"))
      (node (ref "U$12") (pin "+5V@7") (pinfunction "+5V_+5V@7") (pintype "bidirectional"))
      (node (ref "U$12") (pin "+5V@8") (pinfunction "+5V_+5V@8") (pintype "bidirectional"))
      (node (ref "U$12") (pin "+5V@9") (pinfunction "+5V_+5V@9") (pintype "bidirectional"))
      (node (ref "U$15") (pin "VCC@0") (pinfunction "VCC_VCC@0") (pintype "power_in"))
      (node (ref "U$15") (pin "VCC@1") (pinfunction "VCC_VCC@1") (pintype "power_in"))
      (node (ref "U$15") (pin "VCC@2") (pinfunction "VCC_VCC@2") (pintype "power_in"))
      (node (ref "U$15") (pin "VCC@3") (pinfunction "VCC_VCC@3") (pintype "power_in"))
      (node (ref "U1") (pin "24") (pinfunction "VCC_24") (pintype "power_in"))
      (node (ref "U4") (pin "20") (pinfunction "VCC_20") (pintype "power_in"))
      (node (ref "U4") (pin "4") (pinfunction "VCCIO_4") (pintype "power_in"))
    )
    (net (code "79") (name "GND") (class "Default")
      (node (ref "C1") (pin "2") (pinfunction "2_2") (pintype "passive"))
      (node (ref "C10") (pin "2") (pinfunction "2_2") (pintype "passive"))
      (node (ref "C2") (pin "2") (pinfunction "2_2") (pintype "passive"))
      (node (ref "C28") (pin "2") (pinfunction "2_2") (pintype "passive"))
      (node (ref "C29") (pin "2") (pinfunction "2_2") (pintype "passive"))
      (node (ref "C30") (pin "2") (pinfunction "2_2") (pintype "passive"))
      (node (ref "C31") (pin "2") (pinfunction "2_2") (pintype "passive"))
      (node (ref "C32") (pin "2") (pinfunction "2_2") (pintype "passive"))
      (node (ref "C34") (pin "2") (pinfunction "2_2") (pintype "passive"))
      (node (ref "C35") (pin "2") (pinfunction "2_2") (pintype "passive"))
      (node (ref "C5") (pin "2") (pinfunction "2_2") (pintype "passive"))
      (node (ref "C6") (pin "2") (pinfunction "2_2") (pintype "passive"))
      (node (ref "C7") (pin "2") (pinfunction "2_2") (pintype "passive"))
      (node (ref "C8") (pin "2") (pinfunction "2_2") (pintype "passive"))
      (node (ref "C9") (pin "2") (pinfunction "2_2") (pintype "passive"))
      (node (ref "CN1") (pin "1") (pinfunction "1_1") (pintype "passive"))
      (node (ref "CN1") (pin "2") (pinfunction "1_2") (pintype "passive"))
      (node (ref "CN1") (pin "3") (pinfunction "1_3") (pintype "passive"))
      (node (ref "CN1") (pin "4") (pinfunction "1_4") (pintype "passive"))
      (node (ref "CN2") (pin "1") (pinfunction "1_1") (pintype "passive"))
      (node (ref "CN2") (pin "2") (pinfunction "1_2") (pintype "passive"))
      (node (ref "CN2") (pin "3") (pinfunction "1_3") (pintype "passive"))
      (node (ref "CN2") (pin "4") (pinfunction "1_4") (pintype "passive"))
      (node (ref "CN3") (pin "1") (pinfunction "1_1") (pintype "passive"))
      (node (ref "CN3") (pin "2") (pinfunction "1_2") (pintype "passive"))
      (node (ref "CN3") (pin "3") (pinfunction "1_3") (pintype "passive"))
      (node (ref "CN3") (pin "4") (pinfunction "1_4") (pintype "passive"))
      (node (ref "CN4") (pin "1") (pinfunction "1_1") (pintype "passive"))
      (node (ref "CN4") (pin "2") (pinfunction "1_2") (pintype "passive"))
      (node (ref "CN4") (pin "3") (pinfunction "1_3") (pintype "passive"))
      (node (ref "CN4") (pin "4") (pinfunction "1_4") (pintype "passive"))
      (node (ref "GND") (pin "11") (pinfunction "GND_11") (pintype "power_in"))
      (node (ref "GND") (pin "32") (pinfunction "GND1_32") (pintype "power_in"))
      (node (ref "GND") (pin "62") (pinfunction "GND2_62") (pintype "power_in"))
      (node (ref "GND") (pin "81") (pinfunction "GND3_81") (pintype "power_in"))
      (node (ref "GND") (pin "99") (pinfunction "AGND_99") (pintype "power_in"))
      (node (ref "J1") (pin "6") (pinfunction "6_6") (pintype "passive"))
      (node (ref "POWER") (pin "K") (pinfunction "C_K") (pintype "passive"))
      (node (ref "R12") (pin "1") (pinfunction "1_1") (pintype "passive"))
      (node (ref "RESET") (pin "3") (pinfunction "P_3") (pintype "passive"))
      (node (ref "RESET") (pin "4") (pinfunction "P1_4") (pintype "passive"))
      (node (ref "STATUS") (pin "K") (pinfunction "C_K") (pintype "passive"))
      (node (ref "U$10") (pin "GND@10") (pinfunction "GND_GND@10") (pintype "power_in"))
      (node (ref "U$10") (pin "GND@11") (pinfunction "GND_GND@11") (pintype "power_in"))
      (node (ref "U$10") (pin "GND@12") (pinfunction "GND_GND@12") (pintype "power_in"))
      (node (ref "U$10") (pin "GND@13") (pinfunction "GND_GND@13") (pintype "power_in"))
      (node (ref "U$10") (pin "GND@3") (pinfunction "GND_GND@3") (pintype "power_in"))
      (node (ref "U$10") (pin "GND@4") (pinfunction "GND_GND@4") (pintype "power_in"))
      (node (ref "U$10") (pin "GND@5") (pinfunction "GND_GND@5") (pintype "power_in"))
      (node (ref "U$10") (pin "GND@6") (pinfunction "GND_GND@6") (pintype "power_in"))
      (node (ref "U$10") (pin "GND@7") (pinfunction "GND_GND@7") (pintype "power_in"))
      (node (ref "U$10") (pin "GND@8") (pinfunction "GND_GND@8") (pintype "power_in"))
      (node (ref "U$10") (pin "GND@9") (pinfunction "GND_GND@9") (pintype "power_in"))
      (node (ref "U$12") (pin "GND@0") (pinfunction "GND_GND@0") (pintype "bidirectional"))
      (node (ref "U$12") (pin "GND@1") (pinfunction "GND_GND@1") (pintype "bidirectional"))
      (node (ref "U$12") (pin "GND@10") (pinfunction "GND_GND@10") (pintype "bidirectional"))
      (node (ref "U$12") (pin "GND@11") (pinfunction "GND_GND@11") (pintype "bidirectional"))
      (node (ref "U$12") (pin "GND@12") (pinfunction "GND_GND@12") (pintype "bidirectional"))
      (node (ref "U$12") (pin "GND@13") (pinfunction "GND_GND@13") (pintype "bidirectional"))
      (node (ref "U$12") (pin "GND@14") (pinfunction "GND_GND@14") (pintype "bidirectional"))
      (node (ref "U$12") (pin "GND@15") (pinfunction "GND_GND@15") (pintype "bidirectional"))
      (node (ref "U$12") (pin "GND@2") (pinfunction "GND_GND@2") (pintype "bidirectional"))
      (node (ref "U$12") (pin "GND@3") (pinfunction "GND_GND@3") (pintype "bidirectional"))
      (node (ref "U$12") (pin "GND@4") (pinfunction "GND_GND@4") (pintype "bidirectional"))
      (node (ref "U$12") (pin "GND@5") (pinfunction "GND_GND@5") (pintype "bidirectional"))
      (node (ref "U$12") (pin "GND@6") (pinfunction "GND_GND@6") (pintype "bidirectional"))
      (node (ref "U$12") (pin "GND@7") (pinfunction "GND_GND@7") (pintype "bidirectional"))
      (node (ref "U$12") (pin "GND@8") (pinfunction "GND_GND@8") (pintype "bidirectional"))
      (node (ref "U$12") (pin "GND@9") (pinfunction "GND_GND@9") (pintype "bidirectional"))
      (node (ref "U$14") (pin "GND@0") (pinfunction "GND_GND@0") (pintype "power_in"))
      (node (ref "U$14") (pin "GND@1") (pinfunction "GND_GND@1") (pintype "power_in"))
      (node (ref "U$14") (pin "GND@2") (pinfunction "GND_GND@2") (pintype "power_in"))
      (node (ref "U$15") (pin "GND@0") (pinfunction "GND_GND@0") (pintype "power_in"))
      (node (ref "U$15") (pin "GND@1") (pinfunction "GND_GND@1") (pintype "power_in"))
      (node (ref "U$15") (pin "GND@2") (pinfunction "GND_GND@2") (pintype "power_in"))
      (node (ref "U$15") (pin "GND@3") (pinfunction "GND_GND@3") (pintype "power_in"))
      (node (ref "U$2") (pin "GND@0") (pinfunction "GND_GND@0") (pintype "power_in"))
      (node (ref "U$2") (pin "GND@1") (pinfunction "GND_GND@1") (pintype "power_in"))
      (node (ref "U$2") (pin "GND@10") (pinfunction "GND_GND@10") (pintype "power_in"))
      (node (ref "U$2") (pin "GND@11") (pinfunction "GND_GND@11") (pintype "power_in"))
      (node (ref "U$2") (pin "GND@12") (pinfunction "GND_GND@12") (pintype "power_in"))
      (node (ref "U$2") (pin "GND@13") (pinfunction "GND_GND@13") (pintype "power_in"))
      (node (ref "U$2") (pin "GND@14") (pinfunction "GND_GND@14") (pintype "power_in"))
      (node (ref "U$2") (pin "GND@15") (pinfunction "GND_GND@15") (pintype "power_in"))
      (node (ref "U$2") (pin "GND@2") (pinfunction "GND_GND@2") (pintype "power_in"))
      (node (ref "U$2") (pin "GND@3") (pinfunction "GND_GND@3") (pintype "power_in"))
      (node (ref "U$2") (pin "GND@4") (pinfunction "GND_GND@4") (pintype "power_in"))
      (node (ref "U$2") (pin "GND@5") (pinfunction "GND_GND@5") (pintype "power_in"))
      (node (ref "U$2") (pin "GND@6") (pinfunction "GND_GND@6") (pintype "power_in"))
      (node (ref "U$2") (pin "GND@7") (pinfunction "GND_GND@7") (pintype "power_in"))
      (node (ref "U$2") (pin "GND@8") (pinfunction "GND_GND@8") (pintype "power_in"))
      (node (ref "U$2") (pin "GND@9") (pinfunction "GND_GND@9") (pintype "power_in"))
      (node (ref "U1") (pin "1") (pinfunction "GND_1") (pintype "power_in"))
      (node (ref "U4") (pin "18") (pinfunction "GND18_18") (pintype "power_in"))
      (node (ref "U4") (pin "21") (pinfunction "GND21_21") (pintype "power_in"))
      (node (ref "U4") (pin "25") (pinfunction "AGND_25") (pintype "power_in"))
      (node (ref "U4") (pin "26") (pinfunction "TEST_26") (pintype "input"))
      (node (ref "U4") (pin "7") (pinfunction "GND7_7") (pintype "power_in"))
      (node (ref "Y1") (pin "2") (pinfunction "2_2") (pintype "passive"))
    )
    (net (code "80") (name "Net-(F1-Pad1)") (class "Default")
      (node (ref "F1") (pin "1") (pinfunction "1_1") (pintype "bidirectional"))
      (node (ref "U$14") (pin "+5V") (pinfunction "+5V_+5V") (pintype "power_in"))
    )
    (net (code "81") (name "Net-(GND-XTAL1)") (class "Default")
      (node (ref "GND") (pin "34") (pinfunction "XTAL1_34") (pintype "input"))
      (node (ref "Y1") (pin "3") (pinfunction "3_3") (pintype "passive"))
    )
    (net (code "82") (name "Net-(GND-XTAL2)") (class "Default")
      (node (ref "GND") (pin "33") (pinfunction "XTAL2_33") (pintype "output"))
      (node (ref "Y1") (pin "1") (pinfunction "1_1") (pintype "passive"))
    )
    (net (code "83") (name "Net-(POWER-PadA)") (class "Default")
      (node (ref "POWER") (pin "A") (pinfunction "A_A") (pintype "passive"))
      (node (ref "R6") (pin "1") (pinfunction "1_1") (pintype "passive"))
    )
    (net (code "84") (name "Net-(R1-Pad1)") (class "Default")
      (node (ref "R1") (pin "1") (pinfunction "1_1") (pintype "passive"))
      (node (ref "TX") (pin "A") (pinfunction "A_A") (pintype "passive"))
    )
    (net (code "85") (name "Net-(R2-Pad1)") (class "Default")
      (node (ref "R2") (pin "1") (pinfunction "1_1") (pintype "passive"))
      (node (ref "RX") (pin "A") (pinfunction "A_A") (pintype "passive"))
    )
    (net (code "86") (name "Net-(R7-Pad1)") (class "Default")
      (node (ref "R7") (pin "1") (pinfunction "1_1") (pintype "passive"))
      (node (ref "STATUS") (pin "A") (pinfunction "A_A") (pintype "passive"))
    )
    (net (code "87") (name "Net-(U$14-D+)") (class "Default")
      (node (ref "U$14") (pin "+DATA") (pinfunction "D+_+DATA") (pintype "bidirectional"))
      (node (ref "U4") (pin "15") (pinfunction "USBDP_15") (pintype "bidirectional"))
    )
    (net (code "88") (name "Net-(U$14-D-)") (class "Default")
      (node (ref "U$14") (pin "-DATA") (pinfunction "D-_-DATA") (pintype "bidirectional"))
      (node (ref "U4") (pin "16") (pinfunction "USBDM_16") (pintype "bidirectional"))
    )
    (net (code "89") (name "Net-(U1-IREF)") (class "Default")
      (node (ref "R12") (pin "2") (pinfunction "2_2") (pintype "passive"))
      (node (ref "U1") (pin "23") (pinfunction "IREF_23") (pintype "bidirectional"))
    )
    (net (code "90") (name "Net-(U1-OUT0)") (class "Default")
      (node (ref "U$11") (pin "DO0") (pinfunction "DO0_DO0") (pintype "bidirectional"))
      (node (ref "U1") (pin "5") (pinfunction "OUT0_5") (pintype "output"))
    )
    (net (code "91") (name "Net-(U1-OUT1)") (class "Default")
      (node (ref "U$11") (pin "DO1") (pinfunction "DO1_DO1") (pintype "bidirectional"))
      (node (ref "U1") (pin "6") (pinfunction "OUT1_6") (pintype "output"))
    )
    (net (code "92") (name "Net-(U1-OUT2)") (class "Default")
      (node (ref "U$11") (pin "DO2") (pinfunction "DO2_DO2") (pintype "bidirectional"))
      (node (ref "U1") (pin "7") (pinfunction "OUT2_7") (pintype "output"))
    )
    (net (code "93") (name "Net-(U1-OUT3)") (class "Default")
      (node (ref "U$11") (pin "DO3") (pinfunction "DO3_DO3") (pintype "bidirectional"))
      (node (ref "U1") (pin "8") (pinfunction "OUT3_8") (pintype "output"))
    )
    (net (code "94") (name "Net-(U1-OUT4)") (class "Default")
      (node (ref "U$11") (pin "DO4") (pinfunction "DO4_DO4") (pintype "bidirectional"))
      (node (ref "U1") (pin "9") (pinfunction "OUT4_9") (pintype "output"))
    )
    (net (code "95") (name "Net-(U1-OUT5)") (class "Default")
      (node (ref "U$11") (pin "DO5") (pinfunction "DO5_DO5") (pintype "bidirectional"))
      (node (ref "U1") (pin "10") (pinfunction "OUT5_10") (pintype "output"))
    )
    (net (code "96") (name "Net-(U1-OUT6)") (class "Default")
      (node (ref "U$11") (pin "DO6") (pinfunction "DO6_DO6") (pintype "bidirectional"))
      (node (ref "U1") (pin "11") (pinfunction "OUT6_11") (pintype "output"))
    )
    (net (code "97") (name "Net-(U1-OUT7)") (class "Default")
      (node (ref "U$11") (pin "DO7") (pinfunction "DO7_DO7") (pintype "bidirectional"))
      (node (ref "U1") (pin "12") (pinfunction "OUT7_12") (pintype "output"))
    )
    (net (code "98") (name "Net-(U1-OUT8)") (class "Default")
      (node (ref "U$11") (pin "DO8") (pinfunction "DO8_DO8") (pintype "bidirectional"))
      (node (ref "U1") (pin "13") (pinfunction "OUT8_13") (pintype "output"))
    )
    (net (code "99") (name "Net-(U1-OUT9)") (class "Default")
      (node (ref "U$11") (pin "DO9") (pinfunction "DO9_DO9") (pintype "bidirectional"))
      (node (ref "U1") (pin "14") (pinfunction "OUT9_14") (pintype "output"))
    )
    (net (code "100") (name "Net-(U1-OUT10)") (class "Default")
      (node (ref "U$11") (pin "DO10") (pinfunction "DO10_DO10") (pintype "bidirectional"))
      (node (ref "U1") (pin "15") (pinfunction "OUT10_15") (pintype "output"))
    )
    (net (code "101") (name "Net-(U1-OUT11)") (class "Default")
      (node (ref "U$11") (pin "DO11") (pinfunction "DO11_DO11") (pintype "bidirectional"))
      (node (ref "U1") (pin "16") (pinfunction "OUT11_16") (pintype "output"))
    )
    (net (code "102") (name "Net-(U1-OUT12)") (class "Default")
      (node (ref "U$11") (pin "DO12") (pinfunction "DO12_DO12") (pintype "bidirectional"))
      (node (ref "U1") (pin "17") (pinfunction "OUT12_17") (pintype "output"))
    )
    (net (code "103") (name "Net-(U1-OUT13)") (class "Default")
      (node (ref "U$11") (pin "DO13") (pinfunction "DO13_DO13") (pintype "bidirectional"))
      (node (ref "U1") (pin "18") (pinfunction "OUT13_18") (pintype "output"))
    )
    (net (code "104") (name "Net-(U1-OUT14)") (class "Default")
      (node (ref "U$11") (pin "DO14") (pinfunction "DO14_DO14") (pintype "bidirectional"))
      (node (ref "U1") (pin "19") (pinfunction "OUT14_19") (pintype "output"))
    )
    (net (code "105") (name "Net-(U1-OUT15)") (class "Default")
      (node (ref "U$11") (pin "DO15") (pinfunction "DO15_DO15") (pintype "bidirectional"))
      (node (ref "U1") (pin "20") (pinfunction "OUT15_20") (pintype "output"))
    )
    (net (code "106") (name "Net-(U4-3V3OUT)") (class "Default")
      (node (ref "C1") (pin "1") (pinfunction "1_1") (pintype "passive"))
      (node (ref "U4") (pin "17") (pinfunction "3V3OUT_17") (pintype "output"))
    )
    (net (code "107") (name "unconnected-(GND-(CLKO{slash}ICP3{slash}INT7)PE7-Pad9)") (class "Default")
      (node (ref "GND") (pin "9") (pinfunction "(CLKO/ICP3/INT7)PE7_9") (pintype "bidirectional"))
    )
    (net (code "108") (name "unconnected-(GND-(ICP1)PD4-Pad47)") (class "Default")
      (node (ref "GND") (pin "47") (pinfunction "(ICP1)PD4_47") (pintype "bidirectional"))
    )
    (net (code "109") (name "unconnected-(GND-(T1)PD6-Pad49)") (class "Default")
      (node (ref "GND") (pin "49") (pinfunction "(T1)PD6_49") (pintype "bidirectional"))
    )
    (net (code "110") (name "unconnected-(GND-(T3{slash}INT6)PE6-Pad8)") (class "Default")
      (node (ref "GND") (pin "8") (pinfunction "(T3/INT6)PE6_8") (pintype "bidirectional"))
    )
    (net (code "111") (name "unconnected-(GND-(TOSC1)PG4-Pad29)") (class "Default")
      (node (ref "GND") (pin "29") (pinfunction "(TOSC1)PG4_29") (pintype "bidirectional"))
    )
    (net (code "112") (name "unconnected-(GND-(TOSC2)PG3-Pad28)") (class "Default")
      (node (ref "GND") (pin "28") (pinfunction "(TOSC2)PG3_28") (pintype "bidirectional"))
    )
    (net (code "113") (name "unconnected-(GND-(XCK0{slash}AIN0)PE2-Pad4)") (class "Default")
      (node (ref "GND") (pin "4") (pinfunction "(XCK0/AIN0)PE2_4") (pintype "bidirectional"))
    )
    (net (code "114") (name "unconnected-(GND-(XCK1)PD5-Pad48)") (class "Default")
      (node (ref "GND") (pin "48") (pinfunction "(XCK1)PD5_48") (pintype "bidirectional"))
    )
    (net (code "115") (name "unconnected-(GND-PH2(XCK2)-Pad14)") (class "Default")
      (node (ref "GND") (pin "14") (pinfunction "PH2(XCK2)_14") (pintype "bidirectional"))
    )
    (net (code "116") (name "unconnected-(GND-PH7(T4)-Pad27)") (class "Default")
      (node (ref "GND") (pin "27") (pinfunction "PH7(T4)_27") (pintype "bidirectional"))
    )
    (net (code "117") (name "unconnected-(GND-PJ2(XCK3{slash}PCINT11)-Pad65)") (class "Default")
      (node (ref "GND") (pin "65") (pinfunction "PJ2(XCK3/PCINT11)_65") (pintype "bidirectional"))
    )
    (net (code "118") (name "unconnected-(GND-PJ3(PCINT12)-Pad66)") (class "Default")
      (node (ref "GND") (pin "66") (pinfunction "PJ3(PCINT12)_66") (pintype "bidirectional"))
    )
    (net (code "119") (name "unconnected-(GND-PJ4(PCINT13)-Pad67)") (class "Default")
      (node (ref "GND") (pin "67") (pinfunction "PJ4(PCINT13)_67") (pintype "bidirectional"))
    )
    (net (code "120") (name "unconnected-(GND-PJ5(PCINT14)-Pad68)") (class "Default")
      (node (ref "GND") (pin "68") (pinfunction "PJ5(PCINT14)_68") (pintype "bidirectional"))
    )
    (net (code "121") (name "unconnected-(GND-PJ6(PCINT15)-Pad69)") (class "Default")
      (node (ref "GND") (pin "69") (pinfunction "PJ6(PCINT15)_69") (pintype "bidirectional"))
    )
    (net (code "122") (name "unconnected-(GND-PJ7-Pad79)") (class "Default")
      (node (ref "GND") (pin "79") (pinfunction "PJ7_79") (pintype "bidirectional"))
    )
    (net (code "123") (name "unconnected-(U1-SOUT-Pad22)") (class "Default")
      (node (ref "U1") (pin "22") (pinfunction "SOUT_22") (pintype "output"))
    )
    (net (code "124") (name "unconnected-(U4-CTS-Pad11)") (class "Default")
      (node (ref "U4") (pin "11") (pinfunction "CTS_11") (pintype "input"))
    )
    (net (code "125") (name "unconnected-(U4-DCD-Pad10)") (class "Default")
      (node (ref "U4") (pin "10") (pinfunction "DCD_10") (pintype "input"))
    )
    (net (code "126") (name "unconnected-(U4-DSR-Pad9)") (class "Default")
      (node (ref "U4") (pin "9") (pinfunction "DSR_9") (pintype "input"))
    )
    (net (code "127") (name "unconnected-(U4-OSCI-Pad27)") (class "Default")
      (node (ref "U4") (pin "27") (pinfunction "OSCI_27") (pintype "input"))
    )
    (net (code "128") (name "unconnected-(U4-OSCO-Pad28)") (class "Default")
      (node (ref "U4") (pin "28") (pinfunction "OSCO_28") (pintype "output"))
    )
    (net (code "129") (name "unconnected-(U4-PWREN-Pad14)") (class "Default")
      (node (ref "U4") (pin "14") (pinfunction "PWREN_14") (pintype "input"))
    )
    (net (code "130") (name "unconnected-(U4-RESET-Pad19)") (class "Default")
      (node (ref "U4") (pin "19") (pinfunction "RESET_19") (pintype "input"))
    )
    (net (code "131") (name "unconnected-(U4-RI-Pad6)") (class "Default")
      (node (ref "U4") (pin "6") (pinfunction "RI_6") (pintype "input"))
    )
    (net (code "132") (name "unconnected-(U4-RTS-Pad3)") (class "Default")
      (node (ref "U4") (pin "3") (pinfunction "RTS_3") (pintype "output"))
    )
    (net (code "133") (name "unconnected-(U4-SLEEP-Pad12)") (class "Default")
      (node (ref "U4") (pin "12") (pinfunction "SLEEP_12") (pintype "input"))
    )
    (net (code "134") (name "unconnected-(U4-TXDEN-Pad13)") (class "Default")
      (node (ref "U4") (pin "13") (pinfunction "TXDEN_13") (pintype "input"))
    )
  )
)
